# shield.net
KiCad netlist of a schematic drawn in EAGLE
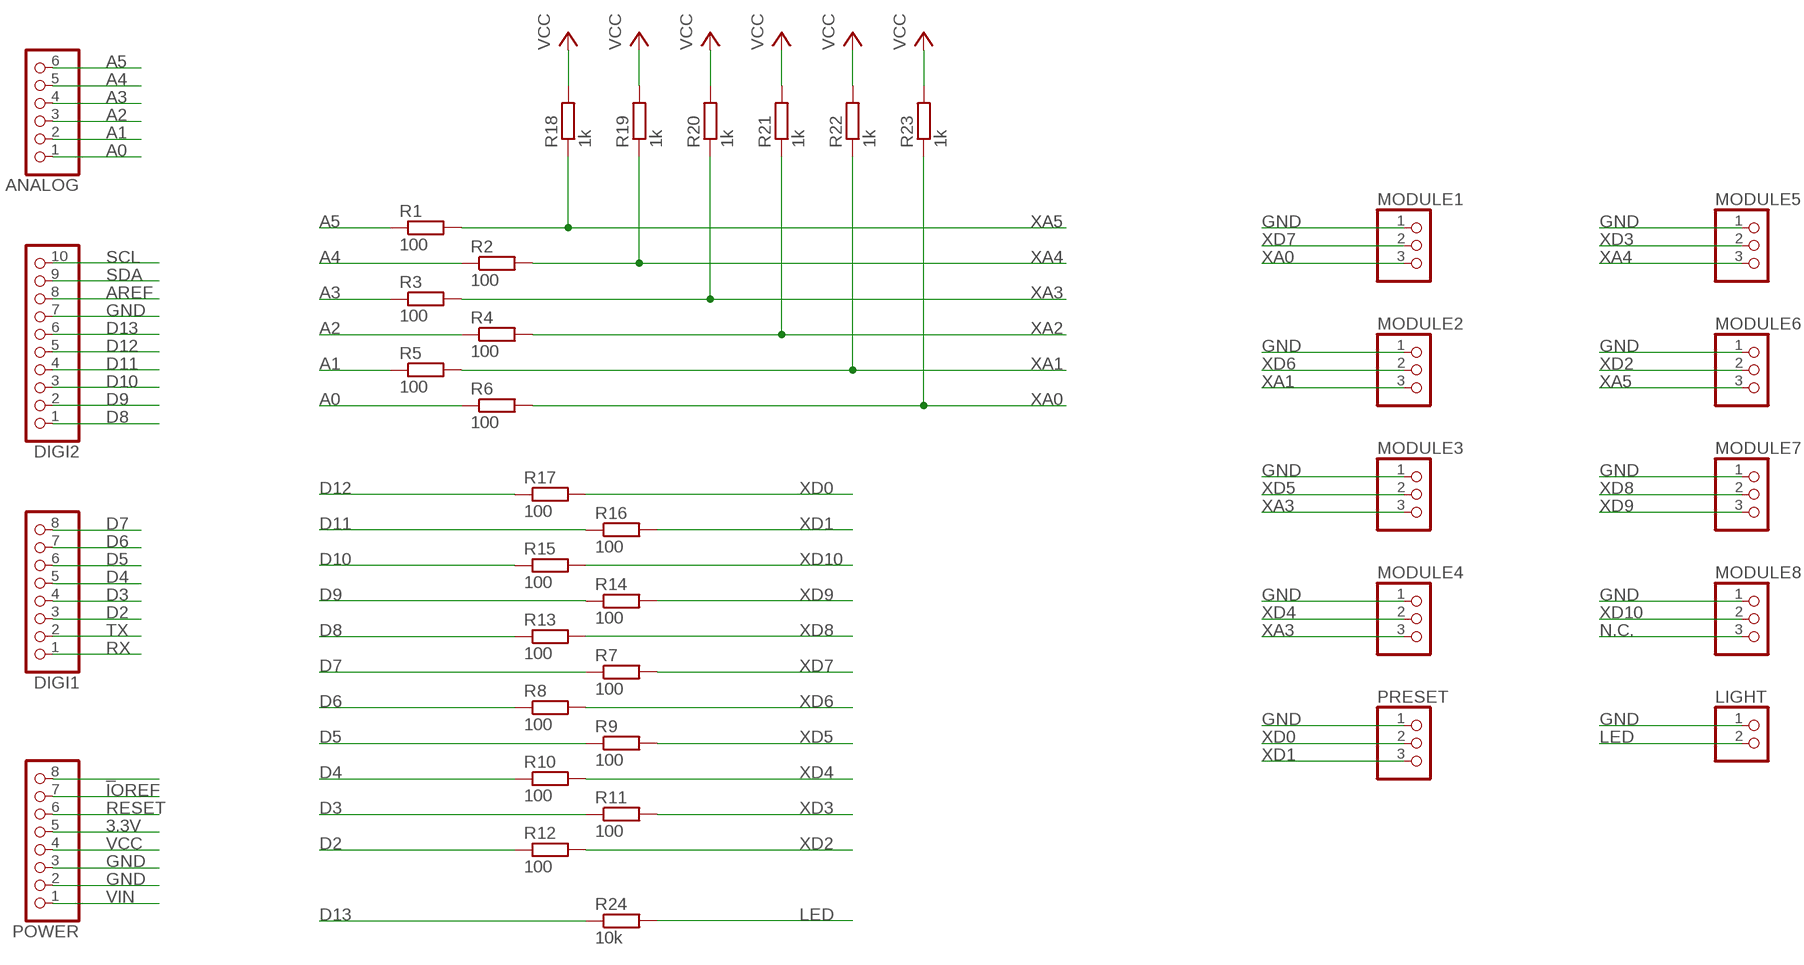
[diagram p0: schematic, sheet 1]

(export (version "E")
  (design (tool "Eeschema 10.0.6"))
  (components
    (comp (ref "ANALOG")
      (value "PINHD-1X6")
      (footprint "eagle-import:1X06")
      (libsource (lib "eagle-import") (part "PINHD-1X6"))
    )
    (comp (ref "DIGI1")
      (value "PINHD-1X8")
      (footprint "eagle-import:1X08")
      (libsource (lib "eagle-import") (part "PINHD-1X8"))
    )
    (comp (ref "DIGI2")
      (value "PINHD-1X10")
      (footprint "eagle-import:1X10")
      (libsource (lib "eagle-import") (part "PINHD-1X10"))
    )
    (comp (ref "LIGHT")
      (value "PINHD-1X2")
      (footprint "eagle-import:1X02")
      (libsource (lib "eagle-import") (part "PINHD-1X2"))
    )
    (comp (ref "MODULE1")
      (value "PINHD-1X3")
      (footprint "eagle-import:1X03")
      (libsource (lib "eagle-import") (part "PINHD-1X3"))
    )
    (comp (ref "MODULE2")
      (value "PINHD-1X3")
      (footprint "eagle-import:1X03")
      (libsource (lib "eagle-import") (part "PINHD-1X3"))
    )
    (comp (ref "MODULE3")
      (value "PINHD-1X3")
      (footprint "eagle-import:1X03")
      (libsource (lib "eagle-import") (part "PINHD-1X3"))
    )
    (comp (ref "MODULE4")
      (value "PINHD-1X3")
      (footprint "eagle-import:1X03")
      (libsource (lib "eagle-import") (part "PINHD-1X3"))
    )
    (comp (ref "MODULE5")
      (value "PINHD-1X3")
      (footprint "eagle-import:1X03")
      (libsource (lib "eagle-import") (part "PINHD-1X3"))
    )
    (comp (ref "MODULE6")
      (value "PINHD-1X3")
      (footprint "eagle-import:1X03")
      (libsource (lib "eagle-import") (part "PINHD-1X3"))
    )
    (comp (ref "MODULE7")
      (value "PINHD-1X3")
      (footprint "eagle-import:1X03")
      (libsource (lib "eagle-import") (part "PINHD-1X3"))
    )
    (comp (ref "MODULE8")
      (value "PINHD-1X3")
      (footprint "eagle-import:1X03")
      (libsource (lib "eagle-import") (part "PINHD-1X3"))
    )
    (comp (ref "POWER")
      (value "PINHD-1X8")
      (footprint "eagle-import:1X08")
      (libsource (lib "eagle-import") (part "PINHD-1X8"))
    )
    (comp (ref "PRESET")
      (value "PINHD-1X3")
      (footprint "eagle-import:1X03")
      (libsource (lib "eagle-import") (part "PINHD-1X3"))
    )
    (comp (ref "R1")
      (value "100")
      (footprint "eagle-import:0207_7")
      (libsource (lib "eagle-import") (part "R-EU_0207/7"))
    )
    (comp (ref "R2")
      (value "100")
      (footprint "eagle-import:0207_7")
      (libsource (lib "eagle-import") (part "R-EU_0207/7"))
    )
    (comp (ref "R3")
      (value "100")
      (footprint "eagle-import:0207_7")
      (libsource (lib "eagle-import") (part "R-EU_0207/7"))
    )
    (comp (ref "R4")
      (value "100")
      (footprint "eagle-import:0207_7")
      (libsource (lib "eagle-import") (part "R-EU_0207/7"))
    )
    (comp (ref "R5")
      (value "100")
      (footprint "eagle-import:0207_7")
      (libsource (lib "eagle-import") (part "R-EU_0207/7"))
    )
    (comp (ref "R6")
      (value "100")
      (footprint "eagle-import:0207_7")
      (libsource (lib "eagle-import") (part "R-EU_0207/7"))
    )
    (comp (ref "R7")
      (value "100")
      (footprint "eagle-import:0207_7")
      (libsource (lib "eagle-import") (part "R-EU_0207/7"))
    )
    (comp (ref "R8")
      (value "100")
      (footprint "eagle-import:0207_7")
      (libsource (lib "eagle-import") (part "R-EU_0207/7"))
    )
    (comp (ref "R9")
      (value "100")
      (footprint "eagle-import:0207_7")
      (libsource (lib "eagle-import") (part "R-EU_0207/7"))
    )
    (comp (ref "R10")
      (value "100")
      (footprint "eagle-import:0207_7")
      (libsource (lib "eagle-import") (part "R-EU_0207/7"))
    )
    (comp (ref "R11")
      (value "100")
      (footprint "eagle-import:0207_7")
      (libsource (lib "eagle-import") (part "R-EU_0207/7"))
    )
    (comp (ref "R12")
      (value "100")
      (footprint "eagle-import:0207_7")
      (libsource (lib "eagle-import") (part "R-EU_0207/7"))
    )
    (comp (ref "R13")
      (value "100")
      (footprint "eagle-import:0207_7")
      (libsource (lib "eagle-import") (part "R-EU_0207/7"))
    )
    (comp (ref "R14")
      (value "100")
      (footprint "eagle-import:0207_7")
      (libsource (lib "eagle-import") (part "R-EU_0207/7"))
    )
    (comp (ref "R15")
      (value "100")
      (footprint "eagle-import:0207_7")
      (libsource (lib "eagle-import") (part "R-EU_0207/7"))
    )
    (comp (ref "R16")
      (value "100")
      (footprint "eagle-import:0207_7")
      (libsource (lib "eagle-import") (part "R-EU_0207/7"))
    )
    (comp (ref "R17")
      (value "100")
      (footprint "eagle-import:0207_7")
      (libsource (lib "eagle-import") (part "R-EU_0207/7"))
    )
    (comp (ref "R18")
      (value "1k")
      (footprint "eagle-import:0207_7")
      (libsource (lib "eagle-import") (part "R-EU_0207/7"))
    )
    (comp (ref "R19")
      (value "1k")
      (footprint "eagle-import:0207_7")
      (libsource (lib "eagle-import") (part "R-EU_0207/7"))
    )
    (comp (ref "R20")
      (value "1k")
      (footprint "eagle-import:0207_7")
      (libsource (lib "eagle-import") (part "R-EU_0207/7"))
    )
    (comp (ref "R21")
      (value "1k")
      (footprint "eagle-import:0207_7")
      (libsource (lib "eagle-import") (part "R-EU_0207/7"))
    )
    (comp (ref "R22")
      (value "1k")
      (footprint "eagle-import:0207_7")
      (libsource (lib "eagle-import") (part "R-EU_0207/7"))
    )
    (comp (ref "R23")
      (value "1k")
      (footprint "eagle-import:0207_7")
      (libsource (lib "eagle-import") (part "R-EU_0207/7"))
    )
    (comp (ref "R24")
      (value "10k")
      (footprint "eagle-import:0207_7")
      (libsource (lib "eagle-import") (part "R-EU_0207/7"))
    )
  )
  (nets
    (net (code "1") (name "/3.3V") (class "Default")
      (node (ref "POWER") (pin "5") (pinfunction "5_5") (pintype "passive"))
    )
    (net (code "2") (name "/A0") (class "Default")
      (node (ref "ANALOG") (pin "1") (pinfunction "1_1") (pintype "passive"))
      (node (ref "R6") (pin "1") (pinfunction "1_1") (pintype "passive"))
    )
    (net (code "3") (name "/A1") (class "Default")
      (node (ref "ANALOG") (pin "2") (pinfunction "2_2") (pintype "passive"))
      (node (ref "R5") (pin "1") (pinfunction "1_1") (pintype "passive"))
    )
    (net (code "4") (name "/A2") (class "Default")
      (node (ref "ANALOG") (pin "3") (pinfunction "3_3") (pintype "passive"))
      (node (ref "R4") (pin "1") (pinfunction "1_1") (pintype "passive"))
    )
    (net (code "5") (name "/A3") (class "Default")
      (node (ref "ANALOG") (pin "4") (pinfunction "4_4") (pintype "passive"))
      (node (ref "R3") (pin "1") (pinfunction "1_1") (pintype "passive"))
    )
    (net (code "6") (name "/A4") (class "Default")
      (node (ref "ANALOG") (pin "5") (pinfunction "5_5") (pintype "passive"))
      (node (ref "R2") (pin "1") (pinfunction "1_1") (pintype "passive"))
    )
    (net (code "7") (name "/A5") (class "Default")
      (node (ref "ANALOG") (pin "6") (pinfunction "6_6") (pintype "passive"))
      (node (ref "R1") (pin "1") (pinfunction "1_1") (pintype "passive"))
    )
    (net (code "8") (name "/AREF") (class "Default")
      (node (ref "DIGI2") (pin "8") (pinfunction "8_8") (pintype "passive"))
    )
    (net (code "9") (name "/D2") (class "Default")
      (node (ref "DIGI1") (pin "3") (pinfunction "3_3") (pintype "passive"))
      (node (ref "R12") (pin "1") (pinfunction "1_1") (pintype "passive"))
    )
    (net (code "10") (name "/D3") (class "Default")
      (node (ref "DIGI1") (pin "4") (pinfunction "4_4") (pintype "passive"))
      (node (ref "R11") (pin "1") (pinfunction "1_1") (pintype "passive"))
    )
    (net (code "11") (name "/D4") (class "Default")
      (node (ref "DIGI1") (pin "5") (pinfunction "5_5") (pintype "passive"))
      (node (ref "R10") (pin "1") (pinfunction "1_1") (pintype "passive"))
    )
    (net (code "12") (name "/D5") (class "Default")
      (node (ref "DIGI1") (pin "6") (pinfunction "6_6") (pintype "passive"))
      (node (ref "R9") (pin "1") (pinfunction "1_1") (pintype "passive"))
    )
    (net (code "13") (name "/D6") (class "Default")
      (node (ref "DIGI1") (pin "7") (pinfunction "7_7") (pintype "passive"))
      (node (ref "R8") (pin "1") (pinfunction "1_1") (pintype "passive"))
    )
    (net (code "14") (name "/D7") (class "Default")
      (node (ref "DIGI1") (pin "8") (pinfunction "8_8") (pintype "passive"))
      (node (ref "R7") (pin "1") (pinfunction "1_1") (pintype "passive"))
    )
    (net (code "15") (name "/D8") (class "Default")
      (node (ref "DIGI2") (pin "1") (pinfunction "1_1") (pintype "passive"))
      (node (ref "R13") (pin "1") (pinfunction "1_1") (pintype "passive"))
    )
    (net (code "16") (name "/D9") (class "Default")
      (node (ref "DIGI2") (pin "2") (pinfunction "2_2") (pintype "passive"))
      (node (ref "R14") (pin "1") (pinfunction "1_1") (pintype "passive"))
    )
    (net (code "17") (name "/D10") (class "Default")
      (node (ref "DIGI2") (pin "3") (pinfunction "3_3") (pintype "passive"))
      (node (ref "R15") (pin "1") (pinfunction "1_1") (pintype "passive"))
    )
    (net (code "18") (name "/D11") (class "Default")
      (node (ref "DIGI2") (pin "4") (pinfunction "4_4") (pintype "passive"))
      (node (ref "R16") (pin "1") (pinfunction "1_1") (pintype "passive"))
    )
    (net (code "19") (name "/D12") (class "Default")
      (node (ref "DIGI2") (pin "5") (pinfunction "5_5") (pintype "passive"))
      (node (ref "R17") (pin "1") (pinfunction "1_1") (pintype "passive"))
    )
    (net (code "20") (name "/D13") (class "Default")
      (node (ref "DIGI2") (pin "6") (pinfunction "6_6") (pintype "passive"))
      (node (ref "R24") (pin "1") (pinfunction "1_1") (pintype "passive"))
    )
    (net (code "21") (name "/GND") (class "Default")
      (node (ref "DIGI2") (pin "7") (pinfunction "7_7") (pintype "passive"))
      (node (ref "LIGHT") (pin "1") (pinfunction "1_1") (pintype "passive"))
      (node (ref "MODULE1") (pin "1") (pinfunction "1_1") (pintype "passive"))
      (node (ref "MODULE2") (pin "1") (pinfunction "1_1") (pintype "passive"))
      (node (ref "MODULE3") (pin "1") (pinfunction "1_1") (pintype "passive"))
      (node (ref "MODULE4") (pin "1") (pinfunction "1_1") (pintype "passive"))
      (node (ref "MODULE5") (pin "1") (pinfunction "1_1") (pintype "passive"))
      (node (ref "MODULE6") (pin "1") (pinfunction "1_1") (pintype "passive"))
      (node (ref "MODULE7") (pin "1") (pinfunction "1_1") (pintype "passive"))
      (node (ref "MODULE8") (pin "1") (pinfunction "1_1") (pintype "passive"))
      (node (ref "POWER") (pin "2") (pinfunction "2_2") (pintype "passive"))
      (node (ref "POWER") (pin "3") (pinfunction "3_3") (pintype "passive"))
      (node (ref "PRESET") (pin "1") (pinfunction "1_1") (pintype "passive"))
    )
    (net (code "22") (name "/IOREF") (class "Default")
      (node (ref "POWER") (pin "7") (pinfunction "7_7") (pintype "passive"))
    )
    (net (code "23") (name "/LED") (class "Default")
      (node (ref "LIGHT") (pin "2") (pinfunction "2_2") (pintype "passive"))
      (node (ref "R24") (pin "2") (pinfunction "2_2") (pintype "passive"))
    )
    (net (code "24") (name "/N.C.") (class "Default")
      (node (ref "MODULE8") (pin "3") (pinfunction "3_3") (pintype "passive"))
    )
    (net (code "25") (name "/RESET") (class "Default")
      (node (ref "POWER") (pin "6") (pinfunction "6_6") (pintype "passive"))
    )
    (net (code "26") (name "/RX") (class "Default")
      (node (ref "DIGI1") (pin "1") (pinfunction "1_1") (pintype "passive"))
    )
    (net (code "27") (name "/SCL") (class "Default")
      (node (ref "DIGI2") (pin "10") (pinfunction "10_10") (pintype "passive"))
    )
    (net (code "28") (name "/SDA") (class "Default")
      (node (ref "DIGI2") (pin "9") (pinfunction "9_9") (pintype "passive"))
    )
    (net (code "29") (name "/TX") (class "Default")
      (node (ref "DIGI1") (pin "2") (pinfunction "2_2") (pintype "passive"))
    )
    (net (code "30") (name "/VIN") (class "Default")
      (node (ref "POWER") (pin "1") (pinfunction "1_1") (pintype "passive"))
    )
    (net (code "31") (name "/XA0") (class "Default")
      (node (ref "MODULE1") (pin "3") (pinfunction "3_3") (pintype "passive"))
      (node (ref "R23") (pin "1") (pinfunction "1_1") (pintype "passive"))
      (node (ref "R6") (pin "2") (pinfunction "2_2") (pintype "passive"))
    )
    (net (code "32") (name "/XA1") (class "Default")
      (node (ref "MODULE2") (pin "3") (pinfunction "3_3") (pintype "passive"))
      (node (ref "R22") (pin "1") (pinfunction "1_1") (pintype "passive"))
      (node (ref "R5") (pin "2") (pinfunction "2_2") (pintype "passive"))
    )
    (net (code "33") (name "/XA2") (class "Default")
      (node (ref "R21") (pin "1") (pinfunction "1_1") (pintype "passive"))
      (node (ref "R4") (pin "2") (pinfunction "2_2") (pintype "passive"))
    )
    (net (code "34") (name "/XA3") (class "Default")
      (node (ref "MODULE3") (pin "3") (pinfunction "3_3") (pintype "passive"))
      (node (ref "MODULE4") (pin "3") (pinfunction "3_3") (pintype "passive"))
      (node (ref "R20") (pin "1") (pinfunction "1_1") (pintype "passive"))
      (node (ref "R3") (pin "2") (pinfunction "2_2") (pintype "passive"))
    )
    (net (code "35") (name "/XA4") (class "Default")
      (node (ref "MODULE5") (pin "3") (pinfunction "3_3") (pintype "passive"))
      (node (ref "R19") (pin "1") (pinfunction "1_1") (pintype "passive"))
      (node (ref "R2") (pin "2") (pinfunction "2_2") (pintype "passive"))
    )
    (net (code "36") (name "/XA5") (class "Default")
      (node (ref "MODULE6") (pin "3") (pinfunction "3_3") (pintype "passive"))
      (node (ref "R1") (pin "2") (pinfunction "2_2") (pintype "passive"))
      (node (ref "R18") (pin "1") (pinfunction "1_1") (pintype "passive"))
    )
    (net (code "37") (name "/XD0") (class "Default")
      (node (ref "PRESET") (pin "2") (pinfunction "2_2") (pintype "passive"))
      (node (ref "R17") (pin "2") (pinfunction "2_2") (pintype "passive"))
    )
    (net (code "38") (name "/XD1") (class "Default")
      (node (ref "PRESET") (pin "3") (pinfunction "3_3") (pintype "passive"))
      (node (ref "R16") (pin "2") (pinfunction "2_2") (pintype "passive"))
    )
    (net (code "39") (name "/XD2") (class "Default")
      (node (ref "MODULE6") (pin "2") (pinfunction "2_2") (pintype "passive"))
      (node (ref "R12") (pin "2") (pinfunction "2_2") (pintype "passive"))
    )
    (net (code "40") (name "/XD3") (class "Default")
      (node (ref "MODULE5") (pin "2") (pinfunction "2_2") (pintype "passive"))
      (node (ref "R11") (pin "2") (pinfunction "2_2") (pintype "passive"))
    )
    (net (code "41") (name "/XD4") (class "Default")
      (node (ref "MODULE4") (pin "2") (pinfunction "2_2") (pintype "passive"))
      (node (ref "R10") (pin "2") (pinfunction "2_2") (pintype "passive"))
    )
    (net (code "42") (name "/XD5") (class "Default")
      (node (ref "MODULE3") (pin "2") (pinfunction "2_2") (pintype "passive"))
      (node (ref "R9") (pin "2") (pinfunction "2_2") (pintype "passive"))
    )
    (net (code "43") (name "/XD6") (class "Default")
      (node (ref "MODULE2") (pin "2") (pinfunction "2_2") (pintype "passive"))
      (node (ref "R8") (pin "2") (pinfunction "2_2") (pintype "passive"))
    )
    (net (code "44") (name "/XD7") (class "Default")
      (node (ref "MODULE1") (pin "2") (pinfunction "2_2") (pintype "passive"))
      (node (ref "R7") (pin "2") (pinfunction "2_2") (pintype "passive"))
    )
    (net (code "45") (name "/XD8") (class "Default")
      (node (ref "MODULE7") (pin "2") (pinfunction "2_2") (pintype "passive"))
      (node (ref "R13") (pin "2") (pinfunction "2_2") (pintype "passive"))
    )
    (net (code "46") (name "/XD9") (class "Default")
      (node (ref "MODULE7") (pin "3") (pinfunction "3_3") (pintype "passive"))
      (node (ref "R14") (pin "2") (pinfunction "2_2") (pintype "passive"))
    )
    (net (code "47") (name "/XD10") (class "Default")
      (node (ref "MODULE8") (pin "2") (pinfunction "2_2") (pintype "passive"))
      (node (ref "R15") (pin "2") (pinfunction "2_2") (pintype "passive"))
    )
    (net (code "48") (name "/_") (class "Default")
      (node (ref "POWER") (pin "8") (pinfunction "8_8") (pintype "passive"))
    )
    (net (code "49") (name "VCC") (class "Default")
      (node (ref "POWER") (pin "4") (pinfunction "4_4") (pintype "passive"))
      (node (ref "R18") (pin "2") (pinfunction "2_2") (pintype "passive"))
      (node (ref "R19") (pin "2") (pinfunction "2_2") (pintype "passive"))
      (node (ref "R20") (pin "2") (pinfunction "2_2") (pintype "passive"))
      (node (ref "R21") (pin "2") (pinfunction "2_2") (pintype "passive"))
      (node (ref "R22") (pin "2") (pinfunction "2_2") (pintype "passive"))
      (node (ref "R23") (pin "2") (pinfunction "2_2") (pintype "passive"))
    )
  )
)
